# StrErfassungMainBoardFinalWide.net
KiCad netlist of a schematic drawn in EAGLE
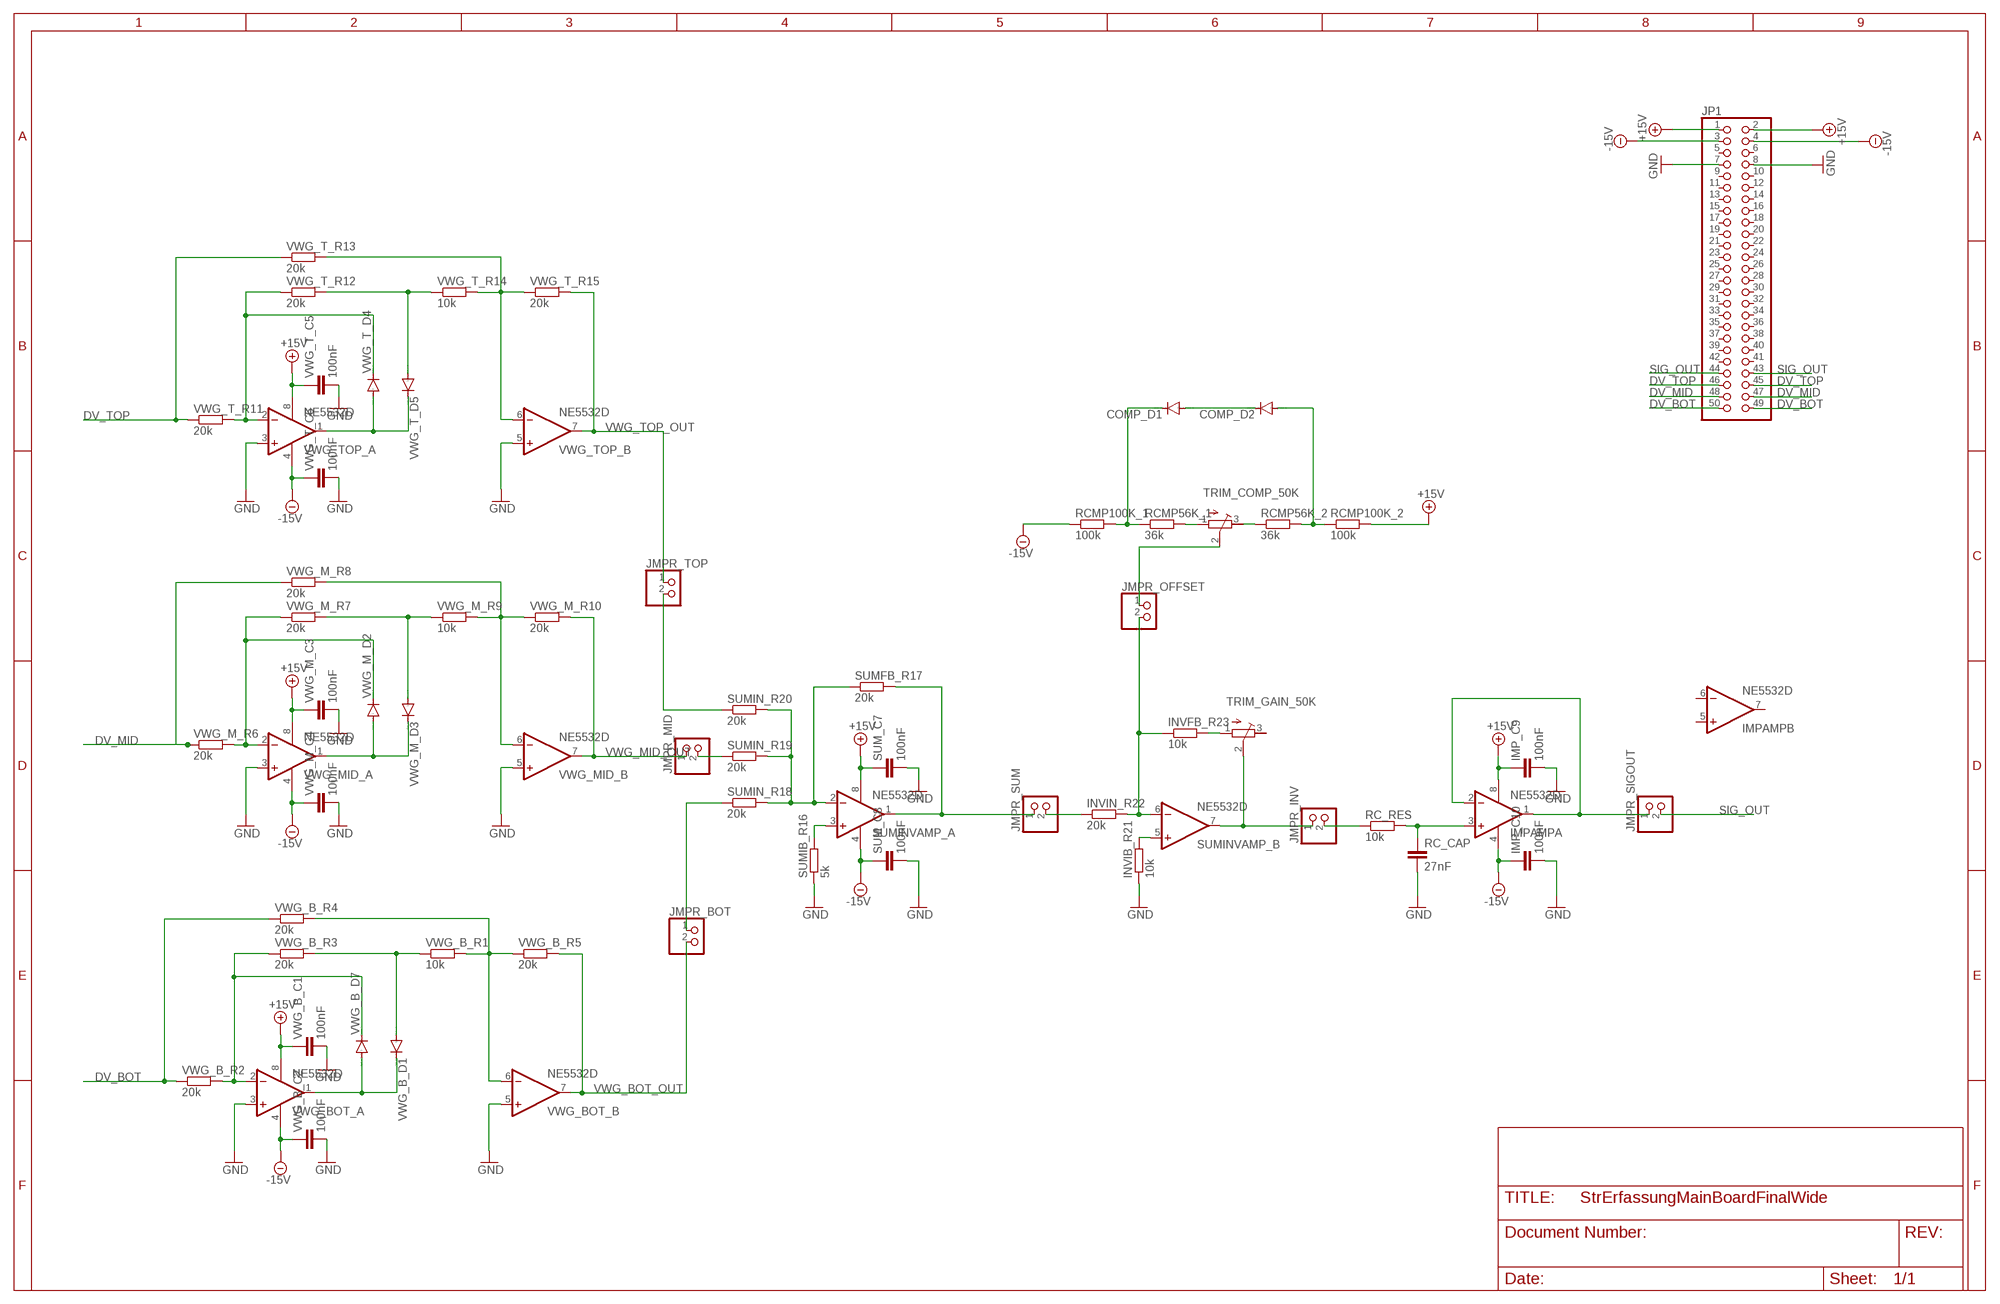
[diagram p0: schematic, sheet 1]

(export (version "E")
  (design (tool "Eeschema 10.0.6"))
  (components
    (comp (ref "COMP_D1")
      (value "DIODE-SOD123")
      (footprint "eagle-import:SOD123")
      (libsource (lib "eagle-import") (part "DIODE-SOD123"))
    )
    (comp (ref "COMP_D2")
      (value "DIODE-SOD123")
      (footprint "eagle-import:SOD123")
      (libsource (lib "eagle-import") (part "DIODE-SOD123"))
    )
    (comp (ref "IMPAMP")
      (value "NE5532D")
      (footprint "eagle-import:SO08")
      (libsource (lib "eagle-import") (part "NE5532D"))
    )
    (comp (ref "IMP_C9")
      (value "100nF")
      (footprint "eagle-import:C0805")
      (libsource (lib "eagle-import") (part "C-EUC0805"))
    )
    (comp (ref "IMP_C10")
      (value "100nF")
      (footprint "eagle-import:C0805")
      (libsource (lib "eagle-import") (part "C-EUC0805"))
    )
    (comp (ref "INVFB_R23")
      (value "10k")
      (footprint "eagle-import:R0805")
      (libsource (lib "eagle-import") (part "R-EU_R0805"))
    )
    (comp (ref "INVIB_R21")
      (value "10k")
      (footprint "eagle-import:R0805")
      (libsource (lib "eagle-import") (part "R-EU_R0805"))
    )
    (comp (ref "INVIN_R22")
      (value "20k")
      (footprint "eagle-import:R0805")
      (libsource (lib "eagle-import") (part "R-EU_R0805"))
    )
    (comp (ref "JMPR_BOT")
      (value "PINHD-1X2")
      (footprint "eagle-import:1X02")
      (libsource (lib "eagle-import") (part "PINHD-1X2"))
    )
    (comp (ref "JMPR_INV")
      (value "PINHD-1X2")
      (footprint "eagle-import:1X02")
      (libsource (lib "eagle-import") (part "PINHD-1X2"))
    )
    (comp (ref "JMPR_MID")
      (value "PINHD-1X2")
      (footprint "eagle-import:1X02")
      (libsource (lib "eagle-import") (part "PINHD-1X2"))
    )
    (comp (ref "JMPR_OFFSET")
      (value "PINHD-1X2")
      (footprint "eagle-import:1X02")
      (libsource (lib "eagle-import") (part "PINHD-1X2"))
    )
    (comp (ref "JMPR_SIGOUT")
      (value "PINHD-1X2")
      (footprint "eagle-import:1X02")
      (libsource (lib "eagle-import") (part "PINHD-1X2"))
    )
    (comp (ref "JMPR_SUM")
      (value "PINHD-1X2")
      (footprint "eagle-import:1X02")
      (libsource (lib "eagle-import") (part "PINHD-1X2"))
    )
    (comp (ref "JMPR_TOP")
      (value "PINHD-1X2")
      (footprint "eagle-import:1X02")
      (libsource (lib "eagle-import") (part "PINHD-1X2"))
    )
    (comp (ref "JP1")
      (value "PINHD-2X25/90")
      (footprint "eagle-import:2X25_90")
      (libsource (lib "eagle-import") (part "PINHD-2X25/90"))
    )
    (comp (ref "RCMP56K_1")
      (value "36k")
      (footprint "eagle-import:R0805")
      (libsource (lib "eagle-import") (part "R-EU_R0805"))
    )
    (comp (ref "RCMP56K_2")
      (value "36k")
      (footprint "eagle-import:R0805")
      (libsource (lib "eagle-import") (part "R-EU_R0805"))
    )
    (comp (ref "RCMP100K_1")
      (value "100k")
      (footprint "eagle-import:R0805")
      (libsource (lib "eagle-import") (part "R-EU_R0805"))
    )
    (comp (ref "RCMP100K_2")
      (value "100k")
      (footprint "eagle-import:R0805")
      (libsource (lib "eagle-import") (part "R-EU_R0805"))
    )
    (comp (ref "RC_CAP")
      (value "27nF")
      (footprint "eagle-import:C0805")
      (libsource (lib "eagle-import") (part "C-EUC0805"))
    )
    (comp (ref "RC_RES")
      (value "10k")
      (footprint "eagle-import:R0805")
      (libsource (lib "eagle-import") (part "R-EU_R0805"))
    )
    (comp (ref "SUMFB_R17")
      (value "20k")
      (footprint "eagle-import:R0805")
      (libsource (lib "eagle-import") (part "R-EU_R0805"))
    )
    (comp (ref "SUMIB_R16")
      (value "5k")
      (footprint "eagle-import:R0805")
      (libsource (lib "eagle-import") (part "R-EU_R0805"))
    )
    (comp (ref "SUMINVAMP_")
      (value "NE5532D")
      (footprint "eagle-import:SO08")
      (libsource (lib "eagle-import") (part "NE5532D"))
    )
    (comp (ref "SUMIN_R18")
      (value "20k")
      (footprint "eagle-import:R0805")
      (libsource (lib "eagle-import") (part "R-EU_R0805"))
    )
    (comp (ref "SUMIN_R19")
      (value "20k")
      (footprint "eagle-import:R0805")
      (libsource (lib "eagle-import") (part "R-EU_R0805"))
    )
    (comp (ref "SUMIN_R20")
      (value "20k")
      (footprint "eagle-import:R0805")
      (libsource (lib "eagle-import") (part "R-EU_R0805"))
    )
    (comp (ref "SUM_C7")
      (value "100nF")
      (footprint "eagle-import:C0805")
      (libsource (lib "eagle-import") (part "C-EUC0805"))
    )
    (comp (ref "SUM_C8")
      (value "100nF")
      (footprint "eagle-import:C0805")
      (libsource (lib "eagle-import") (part "C-EUC0805"))
    )
    (comp (ref "TRIM_COMP_50K")
      (value "R-TRIMM3296W")
      (footprint "eagle-import:RTRIM3296W")
      (libsource (lib "eagle-import") (part "R-TRIMM3296W"))
    )
    (comp (ref "TRIM_GAIN_50K")
      (value "R-TRIMM3296W")
      (footprint "eagle-import:RTRIM3296W")
      (libsource (lib "eagle-import") (part "R-TRIMM3296W"))
    )
    (comp (ref "VWG_BOT_")
      (value "NE5532D")
      (footprint "eagle-import:SO08")
      (libsource (lib "eagle-import") (part "NE5532D"))
    )
    (comp (ref "VWG_B_C1")
      (value "100nF")
      (footprint "eagle-import:C0805")
      (libsource (lib "eagle-import") (part "C-EUC0805"))
    )
    (comp (ref "VWG_B_C2")
      (value "100nF")
      (footprint "eagle-import:C0805")
      (libsource (lib "eagle-import") (part "C-EUC0805"))
    )
    (comp (ref "VWG_B_D1")
      (value "DIODE-SOD123")
      (footprint "eagle-import:SOD123")
      (libsource (lib "eagle-import") (part "DIODE-SOD123"))
    )
    (comp (ref "VWG_B_D7")
      (value "DIODE-SOD123")
      (footprint "eagle-import:SOD123")
      (libsource (lib "eagle-import") (part "DIODE-SOD123"))
    )
    (comp (ref "VWG_B_R1")
      (value "10k")
      (footprint "eagle-import:R0805")
      (libsource (lib "eagle-import") (part "R-EU_R0805"))
    )
    (comp (ref "VWG_B_R2")
      (value "20k")
      (footprint "eagle-import:R0805")
      (libsource (lib "eagle-import") (part "R-EU_R0805"))
    )
    (comp (ref "VWG_B_R3")
      (value "20k")
      (footprint "eagle-import:R0805")
      (libsource (lib "eagle-import") (part "R-EU_R0805"))
    )
    (comp (ref "VWG_B_R4")
      (value "20k")
      (footprint "eagle-import:R0805")
      (libsource (lib "eagle-import") (part "R-EU_R0805"))
    )
    (comp (ref "VWG_B_R5")
      (value "20k")
      (footprint "eagle-import:R0805")
      (libsource (lib "eagle-import") (part "R-EU_R0805"))
    )
    (comp (ref "VWG_MID_")
      (value "NE5532D")
      (footprint "eagle-import:SO08")
      (libsource (lib "eagle-import") (part "NE5532D"))
    )
    (comp (ref "VWG_M_C3")
      (value "100nF")
      (footprint "eagle-import:C0805")
      (libsource (lib "eagle-import") (part "C-EUC0805"))
    )
    (comp (ref "VWG_M_C4")
      (value "100nF")
      (footprint "eagle-import:C0805")
      (libsource (lib "eagle-import") (part "C-EUC0805"))
    )
    (comp (ref "VWG_M_D2")
      (value "DIODE-SOD123")
      (footprint "eagle-import:SOD123")
      (libsource (lib "eagle-import") (part "DIODE-SOD123"))
    )
    (comp (ref "VWG_M_D3")
      (value "DIODE-SOD123")
      (footprint "eagle-import:SOD123")
      (libsource (lib "eagle-import") (part "DIODE-SOD123"))
    )
    (comp (ref "VWG_M_R6")
      (value "20k")
      (footprint "eagle-import:R0805")
      (libsource (lib "eagle-import") (part "R-EU_R0805"))
    )
    (comp (ref "VWG_M_R7")
      (value "20k")
      (footprint "eagle-import:R0805")
      (libsource (lib "eagle-import") (part "R-EU_R0805"))
    )
    (comp (ref "VWG_M_R8")
      (value "20k")
      (footprint "eagle-import:R0805")
      (libsource (lib "eagle-import") (part "R-EU_R0805"))
    )
    (comp (ref "VWG_M_R9")
      (value "10k")
      (footprint "eagle-import:R0805")
      (libsource (lib "eagle-import") (part "R-EU_R0805"))
    )
    (comp (ref "VWG_M_R10")
      (value "20k")
      (footprint "eagle-import:R0805")
      (libsource (lib "eagle-import") (part "R-EU_R0805"))
    )
    (comp (ref "VWG_TOP_")
      (value "NE5532D")
      (footprint "eagle-import:SO08")
      (libsource (lib "eagle-import") (part "NE5532D"))
    )
    (comp (ref "VWG_T_C5")
      (value "100nF")
      (footprint "eagle-import:C0805")
      (libsource (lib "eagle-import") (part "C-EUC0805"))
    )
    (comp (ref "VWG_T_C6")
      (value "100nF")
      (footprint "eagle-import:C0805")
      (libsource (lib "eagle-import") (part "C-EUC0805"))
    )
    (comp (ref "VWG_T_D4")
      (value "DIODE-SOD123")
      (footprint "eagle-import:SOD123")
      (libsource (lib "eagle-import") (part "DIODE-SOD123"))
    )
    (comp (ref "VWG_T_D5")
      (value "DIODE-SOD123")
      (footprint "eagle-import:SOD123")
      (libsource (lib "eagle-import") (part "DIODE-SOD123"))
    )
    (comp (ref "VWG_T_R11")
      (value "20k")
      (footprint "eagle-import:R0805")
      (libsource (lib "eagle-import") (part "R-EU_R0805"))
    )
    (comp (ref "VWG_T_R12")
      (value "20k")
      (footprint "eagle-import:R0805")
      (libsource (lib "eagle-import") (part "R-EU_R0805"))
    )
    (comp (ref "VWG_T_R13")
      (value "20k")
      (footprint "eagle-import:R0805")
      (libsource (lib "eagle-import") (part "R-EU_R0805"))
    )
    (comp (ref "VWG_T_R14")
      (value "10k")
      (footprint "eagle-import:R0805")
      (libsource (lib "eagle-import") (part "R-EU_R0805"))
    )
    (comp (ref "VWG_T_R15")
      (value "20k")
      (footprint "eagle-import:R0805")
      (libsource (lib "eagle-import") (part "R-EU_R0805"))
    )
  )
  (nets
    (net (code "1") (name "+15V") (class "Default")
      (node (ref "IMPAMP") (pin "8") (pinfunction "V+_8") (pintype "power_in"))
      (node (ref "IMP_C9") (pin "1") (pinfunction "1_1") (pintype "passive"))
      (node (ref "JP1") (pin "1") (pinfunction "1_1") (pintype "passive"))
      (node (ref "JP1") (pin "2") (pinfunction "2_2") (pintype "passive"))
      (node (ref "RCMP100K_2") (pin "2") (pinfunction "2_2") (pintype "passive"))
      (node (ref "SUMINVAMP_") (pin "8") (pinfunction "V+_8") (pintype "power_in"))
      (node (ref "SUM_C7") (pin "1") (pinfunction "1_1") (pintype "passive"))
      (node (ref "VWG_BOT_") (pin "8") (pinfunction "V+_8") (pintype "power_in"))
      (node (ref "VWG_B_C1") (pin "1") (pinfunction "1_1") (pintype "passive"))
      (node (ref "VWG_MID_") (pin "8") (pinfunction "V+_8") (pintype "power_in"))
      (node (ref "VWG_M_C3") (pin "1") (pinfunction "1_1") (pintype "passive"))
      (node (ref "VWG_TOP_") (pin "8") (pinfunction "V+_8") (pintype "power_in"))
      (node (ref "VWG_T_C5") (pin "1") (pinfunction "1_1") (pintype "passive"))
    )
    (net (code "2") (name "-15V") (class "Default")
      (node (ref "IMPAMP") (pin "4") (pinfunction "V-_4") (pintype "power_in"))
      (node (ref "IMP_C10") (pin "1") (pinfunction "1_1") (pintype "passive"))
      (node (ref "JP1") (pin "3") (pinfunction "3_3") (pintype "passive"))
      (node (ref "JP1") (pin "4") (pinfunction "4_4") (pintype "passive"))
      (node (ref "RCMP100K_1") (pin "1") (pinfunction "1_1") (pintype "passive"))
      (node (ref "SUMINVAMP_") (pin "4") (pinfunction "V-_4") (pintype "power_in"))
      (node (ref "SUM_C8") (pin "1") (pinfunction "1_1") (pintype "passive"))
      (node (ref "VWG_BOT_") (pin "4") (pinfunction "V-_4") (pintype "power_in"))
      (node (ref "VWG_B_C2") (pin "1") (pinfunction "1_1") (pintype "passive"))
      (node (ref "VWG_MID_") (pin "4") (pinfunction "V-_4") (pintype "power_in"))
      (node (ref "VWG_M_C4") (pin "1") (pinfunction "1_1") (pintype "passive"))
      (node (ref "VWG_TOP_") (pin "4") (pinfunction "V-_4") (pintype "power_in"))
      (node (ref "VWG_T_C6") (pin "1") (pinfunction "1_1") (pintype "passive"))
    )
    (net (code "3") (name "/DV_BOT") (class "Default")
      (node (ref "JP1") (pin "49") (pinfunction "50_49") (pintype "passive"))
      (node (ref "JP1") (pin "50") (pinfunction "49_50") (pintype "passive"))
      (node (ref "VWG_B_R2") (pin "1") (pinfunction "1_1") (pintype "passive"))
      (node (ref "VWG_B_R4") (pin "1") (pinfunction "1_1") (pintype "passive"))
    )
    (net (code "4") (name "/DV_MID") (class "Default")
      (node (ref "JP1") (pin "47") (pinfunction "48_47") (pintype "passive"))
      (node (ref "JP1") (pin "48") (pinfunction "47_48") (pintype "passive"))
      (node (ref "VWG_M_R6") (pin "1") (pinfunction "1_1") (pintype "passive"))
      (node (ref "VWG_M_R8") (pin "1") (pinfunction "1_1") (pintype "passive"))
    )
    (net (code "5") (name "/DV_TOP") (class "Default")
      (node (ref "JP1") (pin "45") (pinfunction "46_45") (pintype "passive"))
      (node (ref "JP1") (pin "46") (pinfunction "45_46") (pintype "passive"))
      (node (ref "VWG_T_R11") (pin "1") (pinfunction "1_1") (pintype "passive"))
      (node (ref "VWG_T_R13") (pin "1") (pinfunction "1_1") (pintype "passive"))
    )
    (net (code "6") (name "/SIG_OUT") (class "Default")
      (node (ref "IMPAMP") (pin "1") (pinfunction "OUT_1") (pintype "output"))
      (node (ref "IMPAMP") (pin "2") (pinfunction "-IN_2") (pintype "input"))
      (node (ref "JMPR_SIGOUT") (pin "1") (pinfunction "1_1") (pintype "passive"))
      (node (ref "JMPR_SIGOUT") (pin "2") (pinfunction "2_2") (pintype "passive"))
      (node (ref "JP1") (pin "43") (pinfunction "44_43") (pintype "passive"))
      (node (ref "JP1") (pin "44") (pinfunction "43_44") (pintype "passive"))
    )
    (net (code "7") (name "/VWG_BOT_OUT") (class "Default")
      (node (ref "JMPR_BOT") (pin "2") (pinfunction "2_2") (pintype "passive"))
      (node (ref "VWG_BOT_") (pin "7") (pinfunction "OUT_7") (pintype "output"))
      (node (ref "VWG_B_R5") (pin "2") (pinfunction "2_2") (pintype "passive"))
    )
    (net (code "8") (name "/VWG_MID_OUT") (class "Default")
      (node (ref "JMPR_MID") (pin "1") (pinfunction "1_1") (pintype "passive"))
      (node (ref "VWG_MID_") (pin "7") (pinfunction "OUT_7") (pintype "output"))
      (node (ref "VWG_M_R10") (pin "2") (pinfunction "2_2") (pintype "passive"))
    )
    (net (code "9") (name "/VWG_TOP_OUT") (class "Default")
      (node (ref "JMPR_TOP") (pin "1") (pinfunction "1_1") (pintype "passive"))
      (node (ref "VWG_TOP_") (pin "7") (pinfunction "OUT_7") (pintype "output"))
      (node (ref "VWG_T_R15") (pin "2") (pinfunction "2_2") (pintype "passive"))
    )
    (net (code "10") (name "GND") (class "Default")
      (node (ref "IMP_C10") (pin "2") (pinfunction "2_2") (pintype "passive"))
      (node (ref "IMP_C9") (pin "2") (pinfunction "2_2") (pintype "passive"))
      (node (ref "INVIB_R21") (pin "1") (pinfunction "1_1") (pintype "passive"))
      (node (ref "JP1") (pin "7") (pinfunction "7_7") (pintype "passive"))
      (node (ref "JP1") (pin "8") (pinfunction "8_8") (pintype "passive"))
      (node (ref "RC_CAP") (pin "2") (pinfunction "2_2") (pintype "passive"))
      (node (ref "SUMIB_R16") (pin "1") (pinfunction "1_1") (pintype "passive"))
      (node (ref "SUM_C7") (pin "2") (pinfunction "2_2") (pintype "passive"))
      (node (ref "SUM_C8") (pin "2") (pinfunction "2_2") (pintype "passive"))
      (node (ref "VWG_BOT_") (pin "3") (pinfunction "+IN_3") (pintype "input"))
      (node (ref "VWG_BOT_") (pin "5") (pinfunction "+IN_5") (pintype "input"))
      (node (ref "VWG_B_C1") (pin "2") (pinfunction "2_2") (pintype "passive"))
      (node (ref "VWG_B_C2") (pin "2") (pinfunction "2_2") (pintype "passive"))
      (node (ref "VWG_MID_") (pin "3") (pinfunction "+IN_3") (pintype "input"))
      (node (ref "VWG_MID_") (pin "5") (pinfunction "+IN_5") (pintype "input"))
      (node (ref "VWG_M_C3") (pin "2") (pinfunction "2_2") (pintype "passive"))
      (node (ref "VWG_M_C4") (pin "2") (pinfunction "2_2") (pintype "passive"))
      (node (ref "VWG_TOP_") (pin "3") (pinfunction "+IN_3") (pintype "input"))
      (node (ref "VWG_TOP_") (pin "5") (pinfunction "+IN_5") (pintype "input"))
      (node (ref "VWG_T_C5") (pin "2") (pinfunction "2_2") (pintype "passive"))
      (node (ref "VWG_T_C6") (pin "2") (pinfunction "2_2") (pintype "passive"))
    )
    (net (code "11") (name "Net-(COMP_D1-PadA)") (class "Default")
      (node (ref "COMP_D1") (pin "A") (pinfunction "A_A") (pintype "passive"))
      (node (ref "COMP_D2") (pin "C") (pinfunction "C_C") (pintype "passive"))
    )
    (net (code "12") (name "Net-(COMP_D1-PadC)") (class "Default")
      (node (ref "COMP_D1") (pin "C") (pinfunction "C_C") (pintype "passive"))
      (node (ref "RCMP100K_1") (pin "2") (pinfunction "2_2") (pintype "passive"))
      (node (ref "RCMP56K_1") (pin "1") (pinfunction "1_1") (pintype "passive"))
    )
    (net (code "13") (name "Net-(COMP_D2-PadA)") (class "Default")
      (node (ref "COMP_D2") (pin "A") (pinfunction "A_A") (pintype "passive"))
      (node (ref "RCMP100K_2") (pin "1") (pinfunction "1_1") (pintype "passive"))
      (node (ref "RCMP56K_2") (pin "2") (pinfunction "2_2") (pintype "passive"))
    )
    (net (code "14") (name "Net-(IMPAMPA-+IN)") (class "Default")
      (node (ref "IMPAMP") (pin "3") (pinfunction "+IN_3") (pintype "input"))
      (node (ref "RC_CAP") (pin "1") (pinfunction "1_1") (pintype "passive"))
      (node (ref "RC_RES") (pin "2") (pinfunction "2_2") (pintype "passive"))
    )
    (net (code "15") (name "Net-(INVIN_R22-Pad1)") (class "Default")
      (node (ref "INVIN_R22") (pin "1") (pinfunction "1_1") (pintype "passive"))
      (node (ref "JMPR_SUM") (pin "2") (pinfunction "2_2") (pintype "passive"))
    )
    (net (code "16") (name "Net-(JMPR_BOT-Pad1)") (class "Default")
      (node (ref "JMPR_BOT") (pin "1") (pinfunction "1_1") (pintype "passive"))
      (node (ref "SUMIN_R18") (pin "1") (pinfunction "1_1") (pintype "passive"))
    )
    (net (code "17") (name "Net-(JMPR_INV-Pad2)") (class "Default")
      (node (ref "JMPR_INV") (pin "2") (pinfunction "2_2") (pintype "passive"))
      (node (ref "RC_RES") (pin "1") (pinfunction "1_1") (pintype "passive"))
    )
    (net (code "18") (name "Net-(JMPR_MID-Pad2)") (class "Default")
      (node (ref "JMPR_MID") (pin "2") (pinfunction "2_2") (pintype "passive"))
      (node (ref "SUMIN_R19") (pin "1") (pinfunction "1_1") (pintype "passive"))
    )
    (net (code "19") (name "Net-(JMPR_TOP-Pad2)") (class "Default")
      (node (ref "JMPR_TOP") (pin "2") (pinfunction "2_2") (pintype "passive"))
      (node (ref "SUMIN_R20") (pin "1") (pinfunction "1_1") (pintype "passive"))
    )
    (net (code "20") (name "Net-(SUMINVAMP_A-+IN)") (class "Default")
      (node (ref "SUMIB_R16") (pin "2") (pinfunction "2_2") (pintype "passive"))
      (node (ref "SUMINVAMP_") (pin "3") (pinfunction "+IN_3") (pintype "input"))
    )
    (net (code "21") (name "Net-(SUMINVAMP_A--IN)") (class "Default")
      (node (ref "SUMFB_R17") (pin "1") (pinfunction "1_1") (pintype "passive"))
      (node (ref "SUMINVAMP_") (pin "2") (pinfunction "-IN_2") (pintype "input"))
      (node (ref "SUMIN_R18") (pin "2") (pinfunction "2_2") (pintype "passive"))
      (node (ref "SUMIN_R19") (pin "2") (pinfunction "2_2") (pintype "passive"))
      (node (ref "SUMIN_R20") (pin "2") (pinfunction "2_2") (pintype "passive"))
    )
    (net (code "22") (name "Net-(SUMINVAMP_A-OUT)") (class "Default")
      (node (ref "JMPR_SUM") (pin "1") (pinfunction "1_1") (pintype "passive"))
      (node (ref "SUMFB_R17") (pin "2") (pinfunction "2_2") (pintype "passive"))
      (node (ref "SUMINVAMP_") (pin "1") (pinfunction "OUT_1") (pintype "output"))
    )
    (net (code "23") (name "Net-(SUMINVAMP_B-+IN)") (class "Default")
      (node (ref "INVIB_R21") (pin "2") (pinfunction "2_2") (pintype "passive"))
      (node (ref "SUMINVAMP_") (pin "5") (pinfunction "+IN_5") (pintype "input"))
    )
    (net (code "24") (name "Net-(SUMINVAMP_B--IN)") (class "Default")
      (node (ref "INVFB_R23") (pin "1") (pinfunction "1_1") (pintype "passive"))
      (node (ref "INVIN_R22") (pin "2") (pinfunction "2_2") (pintype "passive"))
      (node (ref "JMPR_OFFSET") (pin "2") (pinfunction "2_2") (pintype "passive"))
      (node (ref "SUMINVAMP_") (pin "6") (pinfunction "-IN_6") (pintype "input"))
    )
    (net (code "25") (name "Net-(SUMINVAMP_B-OUT)") (class "Default")
      (node (ref "JMPR_INV") (pin "1") (pinfunction "1_1") (pintype "passive"))
      (node (ref "SUMINVAMP_") (pin "7") (pinfunction "OUT_7") (pintype "output"))
      (node (ref "TRIM_GAIN_50K") (pin "2") (pinfunction "S_2") (pintype "passive"))
    )
    (net (code "26") (name "Net-(TRIM_COMP_50K-A)") (class "Default")
      (node (ref "RCMP56K_1") (pin "2") (pinfunction "2_2") (pintype "passive"))
      (node (ref "TRIM_COMP_50K") (pin "1") (pinfunction "A_1") (pintype "passive"))
    )
    (net (code "27") (name "Net-(TRIM_COMP_50K-E)") (class "Default")
      (node (ref "RCMP56K_2") (pin "1") (pinfunction "1_1") (pintype "passive"))
      (node (ref "TRIM_COMP_50K") (pin "3") (pinfunction "E_3") (pintype "passive"))
    )
    (net (code "28") (name "Net-(TRIM_COMP_50K-S)") (class "Default")
      (node (ref "JMPR_OFFSET") (pin "1") (pinfunction "1_1") (pintype "passive"))
      (node (ref "TRIM_COMP_50K") (pin "2") (pinfunction "S_2") (pintype "passive"))
    )
    (net (code "29") (name "Net-(TRIM_GAIN_50K-A)") (class "Default")
      (node (ref "INVFB_R23") (pin "2") (pinfunction "2_2") (pintype "passive"))
      (node (ref "TRIM_GAIN_50K") (pin "1") (pinfunction "A_1") (pintype "passive"))
    )
    (net (code "30") (name "Net-(VWG_BOT_A--IN)") (class "Default")
      (node (ref "VWG_BOT_") (pin "2") (pinfunction "-IN_2") (pintype "input"))
      (node (ref "VWG_B_D7") (pin "C") (pinfunction "C_C") (pintype "passive"))
      (node (ref "VWG_B_R2") (pin "2") (pinfunction "2_2") (pintype "passive"))
      (node (ref "VWG_B_R3") (pin "1") (pinfunction "1_1") (pintype "passive"))
    )
    (net (code "31") (name "Net-(VWG_BOT_A-OUT)") (class "Default")
      (node (ref "VWG_BOT_") (pin "1") (pinfunction "OUT_1") (pintype "output"))
      (node (ref "VWG_B_D1") (pin "C") (pinfunction "C_C") (pintype "passive"))
      (node (ref "VWG_B_D7") (pin "A") (pinfunction "A_A") (pintype "passive"))
    )
    (net (code "32") (name "Net-(VWG_BOT_B--IN)") (class "Default")
      (node (ref "VWG_BOT_") (pin "6") (pinfunction "-IN_6") (pintype "input"))
      (node (ref "VWG_B_R1") (pin "2") (pinfunction "2_2") (pintype "passive"))
      (node (ref "VWG_B_R4") (pin "2") (pinfunction "2_2") (pintype "passive"))
      (node (ref "VWG_B_R5") (pin "1") (pinfunction "1_1") (pintype "passive"))
    )
    (net (code "33") (name "Net-(VWG_B_D1-PadA)") (class "Default")
      (node (ref "VWG_B_D1") (pin "A") (pinfunction "A_A") (pintype "passive"))
      (node (ref "VWG_B_R1") (pin "1") (pinfunction "1_1") (pintype "passive"))
      (node (ref "VWG_B_R3") (pin "2") (pinfunction "2_2") (pintype "passive"))
    )
    (net (code "34") (name "Net-(VWG_MID_A--IN)") (class "Default")
      (node (ref "VWG_MID_") (pin "2") (pinfunction "-IN_2") (pintype "input"))
      (node (ref "VWG_M_D2") (pin "C") (pinfunction "C_C") (pintype "passive"))
      (node (ref "VWG_M_R6") (pin "2") (pinfunction "2_2") (pintype "passive"))
      (node (ref "VWG_M_R7") (pin "1") (pinfunction "1_1") (pintype "passive"))
    )
    (net (code "35") (name "Net-(VWG_MID_A-OUT)") (class "Default")
      (node (ref "VWG_MID_") (pin "1") (pinfunction "OUT_1") (pintype "output"))
      (node (ref "VWG_M_D2") (pin "A") (pinfunction "A_A") (pintype "passive"))
      (node (ref "VWG_M_D3") (pin "C") (pinfunction "C_C") (pintype "passive"))
    )
    (net (code "36") (name "Net-(VWG_MID_B--IN)") (class "Default")
      (node (ref "VWG_MID_") (pin "6") (pinfunction "-IN_6") (pintype "input"))
      (node (ref "VWG_M_R10") (pin "1") (pinfunction "1_1") (pintype "passive"))
      (node (ref "VWG_M_R8") (pin "2") (pinfunction "2_2") (pintype "passive"))
      (node (ref "VWG_M_R9") (pin "2") (pinfunction "2_2") (pintype "passive"))
    )
    (net (code "37") (name "Net-(VWG_M_D3-PadA)") (class "Default")
      (node (ref "VWG_M_D3") (pin "A") (pinfunction "A_A") (pintype "passive"))
      (node (ref "VWG_M_R7") (pin "2") (pinfunction "2_2") (pintype "passive"))
      (node (ref "VWG_M_R9") (pin "1") (pinfunction "1_1") (pintype "passive"))
    )
    (net (code "38") (name "Net-(VWG_TOP_A--IN)") (class "Default")
      (node (ref "VWG_TOP_") (pin "2") (pinfunction "-IN_2") (pintype "input"))
      (node (ref "VWG_T_D4") (pin "C") (pinfunction "C_C") (pintype "passive"))
      (node (ref "VWG_T_R11") (pin "2") (pinfunction "2_2") (pintype "passive"))
      (node (ref "VWG_T_R12") (pin "1") (pinfunction "1_1") (pintype "passive"))
    )
    (net (code "39") (name "Net-(VWG_TOP_A-OUT)") (class "Default")
      (node (ref "VWG_TOP_") (pin "1") (pinfunction "OUT_1") (pintype "output"))
      (node (ref "VWG_T_D4") (pin "A") (pinfunction "A_A") (pintype "passive"))
      (node (ref "VWG_T_D5") (pin "C") (pinfunction "C_C") (pintype "passive"))
    )
    (net (code "40") (name "Net-(VWG_TOP_B--IN)") (class "Default")
      (node (ref "VWG_TOP_") (pin "6") (pinfunction "-IN_6") (pintype "input"))
      (node (ref "VWG_T_R13") (pin "2") (pinfunction "2_2") (pintype "passive"))
      (node (ref "VWG_T_R14") (pin "2") (pinfunction "2_2") (pintype "passive"))
      (node (ref "VWG_T_R15") (pin "1") (pinfunction "1_1") (pintype "passive"))
    )
    (net (code "41") (name "Net-(VWG_T_D5-PadA)") (class "Default")
      (node (ref "VWG_T_D5") (pin "A") (pinfunction "A_A") (pintype "passive"))
      (node (ref "VWG_T_R12") (pin "2") (pinfunction "2_2") (pintype "passive"))
      (node (ref "VWG_T_R14") (pin "1") (pinfunction "1_1") (pintype "passive"))
    )
    (net (code "42") (name "unconnected-(IMPAMPB-+IN-Pad5)") (class "Default")
      (node (ref "IMPAMP") (pin "5") (pinfunction "+IN_5") (pintype "input"))
    )
    (net (code "43") (name "unconnected-(IMPAMPB--IN-Pad6)") (class "Default")
      (node (ref "IMPAMP") (pin "6") (pinfunction "-IN_6") (pintype "input"))
    )
    (net (code "44") (name "unconnected-(IMPAMPB-OUT-Pad7)") (class "Default")
      (node (ref "IMPAMP") (pin "7") (pinfunction "OUT_7") (pintype "output"))
    )
    (net (code "45") (name "unconnected-(JP1-41-Pad42)") (class "Default")
      (node (ref "JP1") (pin "42") (pinfunction "41_42") (pintype "passive"))
    )
    (net (code "46") (name "unconnected-(JP1-42-Pad41)") (class "Default")
      (node (ref "JP1") (pin "41") (pinfunction "42_41") (pintype "passive"))
    )
    (net (code "47") (name "unconnected-(JP1-Pad5)") (class "Default")
      (node (ref "JP1") (pin "5") (pinfunction "5_5") (pintype "passive"))
    )
    (net (code "48") (name "unconnected-(JP1-Pad6)") (class "Default")
      (node (ref "JP1") (pin "6") (pinfunction "6_6") (pintype "passive"))
    )
    (net (code "49") (name "unconnected-(JP1-Pad9)") (class "Default")
      (node (ref "JP1") (pin "9") (pinfunction "9_9") (pintype "passive"))
    )
    (net (code "50") (name "unconnected-(JP1-Pad10)") (class "Default")
      (node (ref "JP1") (pin "10") (pinfunction "10_10") (pintype "passive"))
    )
    (net (code "51") (name "unconnected-(JP1-Pad11)") (class "Default")
      (node (ref "JP1") (pin "11") (pinfunction "11_11") (pintype "passive"))
    )
    (net (code "52") (name "unconnected-(JP1-Pad12)") (class "Default")
      (node (ref "JP1") (pin "12") (pinfunction "12_12") (pintype "passive"))
    )
    (net (code "53") (name "unconnected-(JP1-Pad13)") (class "Default")
      (node (ref "JP1") (pin "13") (pinfunction "13_13") (pintype "passive"))
    )
    (net (code "54") (name "unconnected-(JP1-Pad14)") (class "Default")
      (node (ref "JP1") (pin "14") (pinfunction "14_14") (pintype "passive"))
    )
    (net (code "55") (name "unconnected-(JP1-Pad15)") (class "Default")
      (node (ref "JP1") (pin "15") (pinfunction "15_15") (pintype "passive"))
    )
    (net (code "56") (name "unconnected-(JP1-Pad16)") (class "Default")
      (node (ref "JP1") (pin "16") (pinfunction "16_16") (pintype "passive"))
    )
    (net (code "57") (name "unconnected-(JP1-Pad17)") (class "Default")
      (node (ref "JP1") (pin "17") (pinfunction "17_17") (pintype "passive"))
    )
    (net (code "58") (name "unconnected-(JP1-Pad18)") (class "Default")
      (node (ref "JP1") (pin "18") (pinfunction "18_18") (pintype "passive"))
    )
    (net (code "59") (name "unconnected-(JP1-Pad19)") (class "Default")
      (node (ref "JP1") (pin "19") (pinfunction "19_19") (pintype "passive"))
    )
    (net (code "60") (name "unconnected-(JP1-Pad20)") (class "Default")
      (node (ref "JP1") (pin "20") (pinfunction "20_20") (pintype "passive"))
    )
    (net (code "61") (name "unconnected-(JP1-Pad21)") (class "Default")
      (node (ref "JP1") (pin "21") (pinfunction "21_21") (pintype "passive"))
    )
    (net (code "62") (name "unconnected-(JP1-Pad22)") (class "Default")
      (node (ref "JP1") (pin "22") (pinfunction "22_22") (pintype "passive"))
    )
    (net (code "63") (name "unconnected-(JP1-Pad23)") (class "Default")
      (node (ref "JP1") (pin "23") (pinfunction "23_23") (pintype "passive"))
    )
    (net (code "64") (name "unconnected-(JP1-Pad24)") (class "Default")
      (node (ref "JP1") (pin "24") (pinfunction "24_24") (pintype "passive"))
    )
    (net (code "65") (name "unconnected-(JP1-Pad25)") (class "Default")
      (node (ref "JP1") (pin "25") (pinfunction "25_25") (pintype "passive"))
    )
    (net (code "66") (name "unconnected-(JP1-Pad26)") (class "Default")
      (node (ref "JP1") (pin "26") (pinfunction "26_26") (pintype "passive"))
    )
    (net (code "67") (name "unconnected-(JP1-Pad27)") (class "Default")
      (node (ref "JP1") (pin "27") (pinfunction "27_27") (pintype "passive"))
    )
    (net (code "68") (name "unconnected-(JP1-Pad28)") (class "Default")
      (node (ref "JP1") (pin "28") (pinfunction "28_28") (pintype "passive"))
    )
    (net (code "69") (name "unconnected-(JP1-Pad29)") (class "Default")
      (node (ref "JP1") (pin "29") (pinfunction "29_29") (pintype "passive"))
    )
    (net (code "70") (name "unconnected-(JP1-Pad30)") (class "Default")
      (node (ref "JP1") (pin "30") (pinfunction "30_30") (pintype "passive"))
    )
    (net (code "71") (name "unconnected-(JP1-Pad31)") (class "Default")
      (node (ref "JP1") (pin "31") (pinfunction "31_31") (pintype "passive"))
    )
    (net (code "72") (name "unconnected-(JP1-Pad32)") (class "Default")
      (node (ref "JP1") (pin "32") (pinfunction "32_32") (pintype "passive"))
    )
    (net (code "73") (name "unconnected-(JP1-Pad33)") (class "Default")
      (node (ref "JP1") (pin "33") (pinfunction "33_33") (pintype "passive"))
    )
    (net (code "74") (name "unconnected-(JP1-Pad34)") (class "Default")
      (node (ref "JP1") (pin "34") (pinfunction "34_34") (pintype "passive"))
    )
    (net (code "75") (name "unconnected-(JP1-Pad35)") (class "Default")
      (node (ref "JP1") (pin "35") (pinfunction "35_35") (pintype "passive"))
    )
    (net (code "76") (name "unconnected-(JP1-Pad36)") (class "Default")
      (node (ref "JP1") (pin "36") (pinfunction "36_36") (pintype "passive"))
    )
    (net (code "77") (name "unconnected-(JP1-Pad37)") (class "Default")
      (node (ref "JP1") (pin "37") (pinfunction "37_37") (pintype "passive"))
    )
    (net (code "78") (name "unconnected-(JP1-Pad38)") (class "Default")
      (node (ref "JP1") (pin "38") (pinfunction "38_38") (pintype "passive"))
    )
    (net (code "79") (name "unconnected-(JP1-Pad39)") (class "Default")
      (node (ref "JP1") (pin "39") (pinfunction "39_39") (pintype "passive"))
    )
    (net (code "80") (name "unconnected-(JP1-Pad40)") (class "Default")
      (node (ref "JP1") (pin "40") (pinfunction "40_40") (pintype "passive"))
    )
    (net (code "81") (name "unconnected-(TRIM_GAIN_50K-E-Pad3)") (class "Default")
      (node (ref "TRIM_GAIN_50K") (pin "3") (pinfunction "E_3") (pintype "passive"))
    )
  )
)
